# 7_RS485_RS232_Sensor.net
KiCad netlist of a schematic drawn in Altium Designer
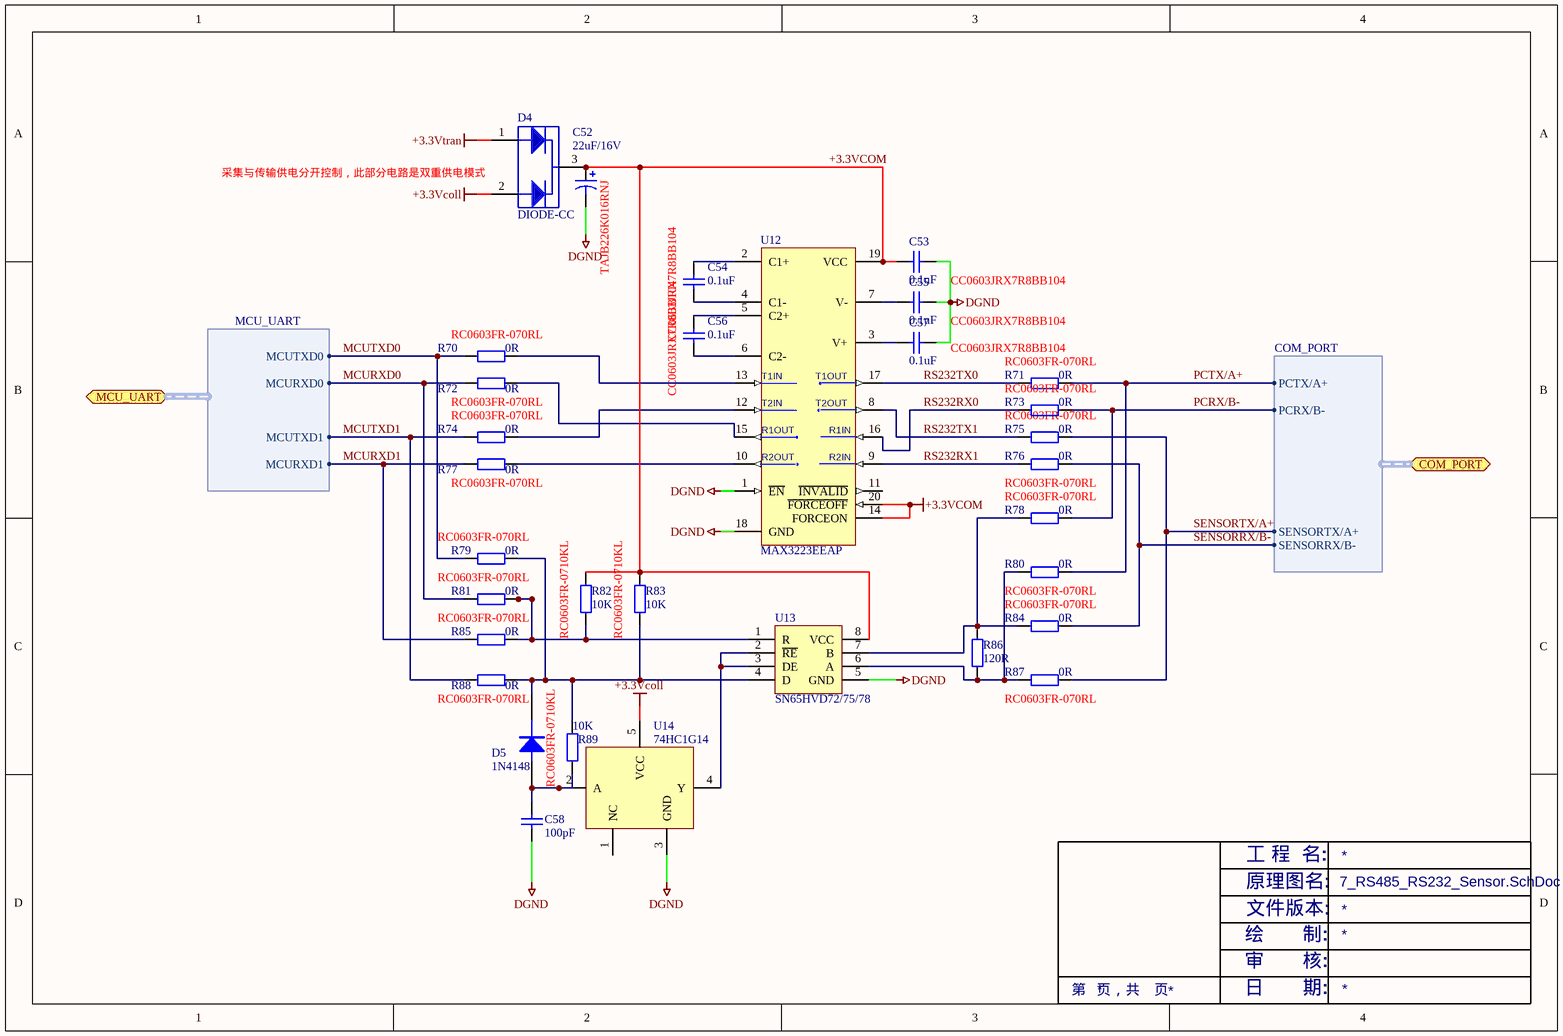
[diagram p0: 7_RS485_RS232_Sensor.SchDoc]

(export (version "E")
  (design (tool "Eeschema 10.0.6"))
  (components
    (comp (ref "C52")
      (value "22uF/16V")
      (footprint "CB3528")
      (description "Polarized Capacitor (Radial)")
      (fields (field (name "PART NO.") "TAJB226K016RNJ"))
      (libsource (lib "Miscellaneous Devices") (part "Cap Pol1"))
    )
    (comp (ref "C53")
      (value "0.1uF")
      (footprint "CC0603")
      (description "Capacitor")
      (fields (field (name "TYPE NO.") "CC0603JRX7R8BB104"))
      (libsource (lib "Miscellaneous Devices") (part "Cap"))
    )
    (comp (ref "C54")
      (value "0.1uF")
      (footprint "CC0603")
      (description "Capacitor")
      (fields (field (name "TYPE NO.") "CC0603JRX7R8BB104"))
      (libsource (lib "Miscellaneous Devices") (part "Cap"))
    )
    (comp (ref "C55")
      (value "0.1uF")
      (footprint "CC0603")
      (description "Capacitor")
      (fields (field (name "TYPE NO.") "CC0603JRX7R8BB104"))
      (libsource (lib "Miscellaneous Devices") (part "Cap"))
    )
    (comp (ref "C56")
      (value "0.1uF")
      (footprint "CC0603")
      (description "Capacitor")
      (fields (field (name "TYPE NO.") "CC0603JRX7R8BB104"))
      (libsource (lib "Miscellaneous Devices") (part "Cap"))
    )
    (comp (ref "C57")
      (value "0.1uF")
      (footprint "CC0603")
      (description "Capacitor")
      (fields (field (name "TYPE NO.") "CC0603JRX7R8BB104"))
      (libsource (lib "Miscellaneous Devices") (part "Cap"))
    )
    (comp (ref "C58")
      (value "100pF")
      (footprint "CC0603")
      (description "Capacitor")
      (libsource (lib "Miscellaneous Devices") (part "Cap"))
    )
    (comp (ref "D4")
      (value "DIODE-CC")
      (footprint "SOT-23W")
      (libsource (lib "woylib2015") (part "DIODE-CC"))
    )
    (comp (ref "D5") (value "1N4148") (footprint "SOD323") (libsource (lib "woylib2015") (part "DIODE")))
    (comp (ref "R70")
      (value "0R")
      (footprint "CC0603")
      (description "Resistor")
      (fields (field (name "TYPE NO.") "RC0603FR-070RL"))
      (libsource (lib "Miscellaneous Devices") (part "Res2"))
    )
    (comp (ref "R71")
      (value "0R")
      (footprint "CC0603")
      (description "Resistor")
      (fields (field (name "TYPE NO.") "RC0603FR-070RL"))
      (libsource (lib "Miscellaneous Devices") (part "Res2"))
    )
    (comp (ref "R72")
      (value "0R")
      (footprint "CC0603")
      (description "Resistor")
      (fields (field (name "TYPE NO.") "RC0603FR-070RL"))
      (libsource (lib "Miscellaneous Devices") (part "Res2"))
    )
    (comp (ref "R73")
      (value "0R")
      (footprint "CC0603")
      (description "Resistor")
      (fields (field (name "TYPE NO.") "RC0603FR-070RL"))
      (libsource (lib "Miscellaneous Devices") (part "Res2"))
    )
    (comp (ref "R74")
      (value "0R")
      (footprint "CC0603")
      (description "Resistor")
      (fields (field (name "TYPE NO.") "RC0603FR-070RL"))
      (libsource (lib "Miscellaneous Devices") (part "Res2"))
    )
    (comp (ref "R75")
      (value "0R")
      (footprint "CC0603")
      (description "Resistor")
      (fields (field (name "TYPE NO.") "RC0603FR-070RL"))
      (libsource (lib "Miscellaneous Devices") (part "Res2"))
    )
    (comp (ref "R76")
      (value "0R")
      (footprint "CC0603")
      (description "Resistor")
      (fields (field (name "TYPE NO.") "RC0603FR-070RL"))
      (libsource (lib "Miscellaneous Devices") (part "Res2"))
    )
    (comp (ref "R77")
      (value "0R")
      (footprint "CC0603")
      (description "Resistor")
      (fields (field (name "TYPE NO.") "RC0603FR-070RL"))
      (libsource (lib "Miscellaneous Devices") (part "Res2"))
    )
    (comp (ref "R78")
      (value "0R")
      (footprint "CC0603")
      (description "Resistor")
      (fields (field (name "TYPE NO.") "RC0603FR-070RL"))
      (libsource (lib "Miscellaneous Devices") (part "Res2"))
    )
    (comp (ref "R79")
      (value "0R")
      (footprint "CC0603")
      (description "Resistor")
      (fields (field (name "TYPE NO.") "RC0603FR-070RL"))
      (libsource (lib "Miscellaneous Devices") (part "Res2"))
    )
    (comp (ref "R80")
      (value "0R")
      (footprint "CC0603")
      (description "Resistor")
      (fields (field (name "TYPE NO.") "RC0603FR-070RL"))
      (libsource (lib "Miscellaneous Devices") (part "Res2"))
    )
    (comp (ref "R81")
      (value "0R")
      (footprint "CC0603")
      (description "Resistor")
      (fields (field (name "TYPE NO.") "RC0603FR-070RL"))
      (libsource (lib "Miscellaneous Devices") (part "Res2"))
    )
    (comp (ref "R82")
      (value "10K")
      (footprint "CC0603")
      (description "Resistor")
      (fields (field (name "TYPE NO.") "RC0603FR-0710KL"))
      (libsource (lib "") (part "Res2_1"))
    )
    (comp (ref "R83")
      (value "10K")
      (footprint "CC0603")
      (description "Resistor")
      (fields (field (name "TYPE NO.") "RC0603FR-0710KL"))
      (libsource (lib "") (part "Res2_1"))
    )
    (comp (ref "R84")
      (value "0R")
      (footprint "CC0603")
      (description "Resistor")
      (fields (field (name "TYPE NO.") "RC0603FR-070RL"))
      (libsource (lib "Miscellaneous Devices") (part "Res2"))
    )
    (comp (ref "R85")
      (value "0R")
      (footprint "CC0603")
      (description "Resistor")
      (fields (field (name "TYPE NO.") "RC0603FR-070RL"))
      (libsource (lib "Miscellaneous Devices") (part "Res2"))
    )
    (comp (ref "R86")
      (value "120R")
      (footprint "CC0603")
      (description "Resistor")
      (fields (field (name "PUBLISHER") "Altium Limited"))
      (libsource (lib "") (part "Res2_1"))
    )
    (comp (ref "R87")
      (value "0R")
      (footprint "CC0603")
      (description "Resistor")
      (fields (field (name "TYPE NO.") "RC0603FR-070RL"))
      (libsource (lib "Miscellaneous Devices") (part "Res2"))
    )
    (comp (ref "R88")
      (value "0R")
      (footprint "CC0603")
      (description "Resistor")
      (fields (field (name "TYPE NO.") "RC0603FR-070RL"))
      (libsource (lib "Miscellaneous Devices") (part "Res2"))
    )
    (comp (ref "R89")
      (value "10K")
      (footprint "CC0603")
      (description "Resistor")
      (fields (field (name "TYPE NO.") "RC0603FR-0710KL"))
      (libsource (lib "") (part "Res2_1"))
    )
    (comp (ref "U12") (value "MAX3223EEAP") (footprint "TSSOP20") (libsource (lib "IC") (part "MAX3223EEAP")))
    (comp (ref "U13")
      (value "SN65HVD72/75/78")
      (footprint "SO-8")
      (libsource (lib "IC") (part "SN65HVD72/75/78"))
    )
    (comp (ref "U14")
      (value "74HC1G14")
      (footprint "SOT-23-5")
      (libsource (lib "woylib2015") (part "74HC1G14"))
    )
  )
  (nets
    (net (code "3") (name "+3.3VCOM") (class "Default")
      (node (ref "C52") (pin "1") (pinfunction "1_1") (pintype "passive"))
      (node (ref "C53") (pin "2") (pinfunction "2_2") (pintype "passive"))
      (node (ref "D4") (pin "3") (pinfunction "3_3") (pintype "passive"))
      (node (ref "R82") (pin "2") (pinfunction "2_2") (pintype "passive"))
      (node (ref "R83") (pin "2") (pinfunction "2_2") (pintype "passive"))
      (node (ref "U12") (pin "14") (pinfunction "FORCEON_14") (pintype "passive"))
      (node (ref "U12") (pin "19") (pinfunction "VCC_19") (pintype "power_in"))
      (node (ref "U12") (pin "20") (pinfunction "~{FORCEOFF}_20") (pintype "input"))
      (node (ref "U13") (pin "8") (pinfunction "VCC_8") (pintype "passive"))
    )
    (net (code "4") (name "+3.3Vcoll") (class "Default")
      (node (ref "D4") (pin "2") (pinfunction "2_2") (pintype "passive"))
      (node (ref "U14") (pin "5") (pinfunction "VCC_5") (pintype "passive"))
    )
    (net (code "5") (name "+3.3Vtran") (class "Default")
      (node (ref "D4") (pin "1") (pinfunction "1_1") (pintype "passive"))
    )
    (net (code "6") (name "/MCURXD0") (class "Default")
      (node (ref "R72") (pin "1") (pinfunction "1_1") (pintype "passive"))
      (node (ref "R81") (pin "1") (pinfunction "1_1") (pintype "passive"))
    )
    (net (code "7") (name "/MCURXD1") (class "Default")
      (node (ref "R77") (pin "1") (pinfunction "1_1") (pintype "passive"))
      (node (ref "R85") (pin "1") (pinfunction "1_1") (pintype "passive"))
    )
    (net (code "8") (name "/MCUTXD0") (class "Default")
      (node (ref "R70") (pin "1") (pinfunction "1_1") (pintype "passive"))
      (node (ref "R79") (pin "1") (pinfunction "1_1") (pintype "passive"))
    )
    (net (code "9") (name "/MCUTXD1") (class "Default")
      (node (ref "R74") (pin "1") (pinfunction "1_1") (pintype "passive"))
      (node (ref "R88") (pin "1") (pinfunction "1_1") (pintype "passive"))
    )
    (net (code "10") (name "/PCRX{slash}B-") (class "Default")
      (node (ref "R73") (pin "2") (pinfunction "2_2") (pintype "passive"))
      (node (ref "R78") (pin "2") (pinfunction "2_2") (pintype "passive"))
    )
    (net (code "11") (name "/PCTX{slash}A+") (class "Default")
      (node (ref "R71") (pin "2") (pinfunction "2_2") (pintype "passive"))
      (node (ref "R80") (pin "2") (pinfunction "2_2") (pintype "passive"))
    )
    (net (code "12") (name "/RS232RX0") (class "Default")
      (node (ref "R73") (pin "1") (pinfunction "1_1") (pintype "passive"))
      (node (ref "U12") (pin "16") (pinfunction "R1IN_16") (pintype "input"))
    )
    (net (code "13") (name "/RS232RX1") (class "Default")
      (node (ref "R76") (pin "1") (pinfunction "1_1") (pintype "passive"))
      (node (ref "U12") (pin "9") (pinfunction "R2IN_9") (pintype "input"))
    )
    (net (code "14") (name "/RS232TX0") (class "Default")
      (node (ref "R71") (pin "1") (pinfunction "1_1") (pintype "passive"))
      (node (ref "U12") (pin "17") (pinfunction "T1OUT_17") (pintype "output"))
    )
    (net (code "15") (name "/RS232TX1") (class "Default")
      (node (ref "R75") (pin "1") (pinfunction "1_1") (pintype "passive"))
      (node (ref "U12") (pin "8") (pinfunction "T2OUT_8") (pintype "output"))
    )
    (net (code "16") (name "/SENSORRX{slash}B-") (class "Default")
      (node (ref "R76") (pin "2") (pinfunction "2_2") (pintype "passive"))
      (node (ref "R84") (pin "2") (pinfunction "2_2") (pintype "passive"))
    )
    (net (code "17") (name "/SENSORTX{slash}A+") (class "Default")
      (node (ref "R75") (pin "2") (pinfunction "2_2") (pintype "passive"))
      (node (ref "R87") (pin "2") (pinfunction "2_2") (pintype "passive"))
    )
    (net (code "20") (name "DGND") (class "Default")
      (node (ref "C52") (pin "2") (pinfunction "2_2") (pintype "passive"))
      (node (ref "C53") (pin "1") (pinfunction "1_1") (pintype "passive"))
      (node (ref "C55") (pin "1") (pinfunction "1_1") (pintype "passive"))
      (node (ref "C57") (pin "1") (pinfunction "1_1") (pintype "passive"))
      (node (ref "C58") (pin "1") (pinfunction "1_1") (pintype "passive"))
      (node (ref "U12") (pin "1") (pinfunction "~{EN}_1") (pintype "input"))
      (node (ref "U12") (pin "18") (pinfunction "GND_18") (pintype "power_in"))
      (node (ref "U13") (pin "5") (pinfunction "GND_5") (pintype "passive"))
      (node (ref "U14") (pin "3") (pinfunction "GND_3") (pintype "passive"))
    )
    (net (code "21") (name "Net-(D5-A)") (class "Default")
      (node (ref "C58") (pin "2") (pinfunction "2_2") (pintype "passive"))
      (node (ref "D5") (pin "1") (pinfunction "A_1") (pintype "passive"))
      (node (ref "R89") (pin "1") (pinfunction "1_1") (pintype "passive"))
      (node (ref "U14") (pin "2") (pinfunction "A_2") (pintype "passive"))
    )
    (net (code "22") (name "Net-(D5-K)") (class "Default")
      (node (ref "D5") (pin "2") (pinfunction "K_2") (pintype "passive"))
      (node (ref "R79") (pin "2") (pinfunction "2_2") (pintype "passive"))
      (node (ref "R83") (pin "1") (pinfunction "1_1") (pintype "passive"))
      (node (ref "R88") (pin "2") (pinfunction "2_2") (pintype "passive"))
      (node (ref "R89") (pin "2") (pinfunction "2_2") (pintype "passive"))
      (node (ref "U13") (pin "4") (pinfunction "D_4") (pintype "passive"))
    )
    (net (code "23") (name "Net-(U12-C1+)") (class "Default")
      (node (ref "C54") (pin "2") (pinfunction "2_2") (pintype "passive"))
      (node (ref "U12") (pin "2") (pinfunction "C1+_2") (pintype "passive"))
    )
    (net (code "24") (name "Net-(U12-C1-)") (class "Default")
      (node (ref "C54") (pin "1") (pinfunction "1_1") (pintype "passive"))
      (node (ref "U12") (pin "4") (pinfunction "C1-_4") (pintype "passive"))
    )
    (net (code "25") (name "Net-(U12-C2+)") (class "Default")
      (node (ref "C56") (pin "2") (pinfunction "2_2") (pintype "passive"))
      (node (ref "U12") (pin "5") (pinfunction "C2+_5") (pintype "passive"))
    )
    (net (code "26") (name "Net-(U12-C2-)") (class "Default")
      (node (ref "C56") (pin "1") (pinfunction "1_1") (pintype "passive"))
      (node (ref "U12") (pin "6") (pinfunction "C2-_6") (pintype "passive"))
    )
    (net (code "27") (name "Net-(U12-R1OUT)") (class "Default")
      (node (ref "R72") (pin "2") (pinfunction "2_2") (pintype "passive"))
      (node (ref "U12") (pin "15") (pinfunction "R1OUT_15") (pintype "output"))
    )
    (net (code "28") (name "Net-(U12-R2OUT)") (class "Default")
      (node (ref "R77") (pin "2") (pinfunction "2_2") (pintype "passive"))
      (node (ref "U12") (pin "10") (pinfunction "R2OUT_10") (pintype "output"))
    )
    (net (code "29") (name "Net-(U12-T1IN)") (class "Default")
      (node (ref "R70") (pin "2") (pinfunction "2_2") (pintype "passive"))
      (node (ref "U12") (pin "13") (pinfunction "T1IN_13") (pintype "input"))
    )
    (net (code "30") (name "Net-(U12-T2IN)") (class "Default")
      (node (ref "R74") (pin "2") (pinfunction "2_2") (pintype "passive"))
      (node (ref "U12") (pin "12") (pinfunction "T2IN_12") (pintype "input"))
    )
    (net (code "31") (name "Net-(U12-V+)") (class "Default")
      (node (ref "C57") (pin "2") (pinfunction "2_2") (pintype "passive"))
      (node (ref "U12") (pin "3") (pinfunction "V+_3") (pintype "power_in"))
    )
    (net (code "32") (name "Net-(U12-V-)") (class "Default")
      (node (ref "C55") (pin "2") (pinfunction "2_2") (pintype "passive"))
      (node (ref "U12") (pin "7") (pinfunction "V-_7") (pintype "power_in"))
    )
    (net (code "33") (name "Net-(U13-A)") (class "Default")
      (node (ref "R80") (pin "1") (pinfunction "1_1") (pintype "passive"))
      (node (ref "R86") (pin "1") (pinfunction "1_1") (pintype "passive"))
      (node (ref "R87") (pin "1") (pinfunction "1_1") (pintype "passive"))
      (node (ref "U13") (pin "6") (pinfunction "A_6") (pintype "passive"))
    )
    (net (code "34") (name "Net-(U13-B)") (class "Default")
      (node (ref "R78") (pin "1") (pinfunction "1_1") (pintype "passive"))
      (node (ref "R84") (pin "1") (pinfunction "1_1") (pintype "passive"))
      (node (ref "R86") (pin "2") (pinfunction "2_2") (pintype "passive"))
      (node (ref "U13") (pin "7") (pinfunction "B_7") (pintype "passive"))
    )
    (net (code "35") (name "Net-(U13-DE)") (class "Default")
      (node (ref "U13") (pin "2") (pinfunction "~{RE}_2") (pintype "passive"))
      (node (ref "U13") (pin "3") (pinfunction "DE_3") (pintype "passive"))
      (node (ref "U14") (pin "4") (pinfunction "Y_4") (pintype "passive"))
    )
    (net (code "36") (name "Net-(U13-R)") (class "Default")
      (node (ref "R81") (pin "2") (pinfunction "2_2") (pintype "passive"))
      (node (ref "R82") (pin "1") (pinfunction "1_1") (pintype "passive"))
      (node (ref "R85") (pin "2") (pinfunction "2_2") (pintype "passive"))
      (node (ref "U13") (pin "1") (pinfunction "R_1") (pintype "passive"))
    )
    (net (code "37") (name "unconnected-(U12-~{INVALID}-Pad11)") (class "Default")
      (node (ref "U12") (pin "11") (pinfunction "~{INVALID}_11") (pintype "output"))
    )
    (net (code "38") (name "unconnected-(U14-NC-Pad1)") (class "Default")
      (node (ref "U14") (pin "1") (pinfunction "NC_1") (pintype "passive"))
    )
  )
)
